# evm_1.net
KiCad netlist of a schematic drawn in EAGLE
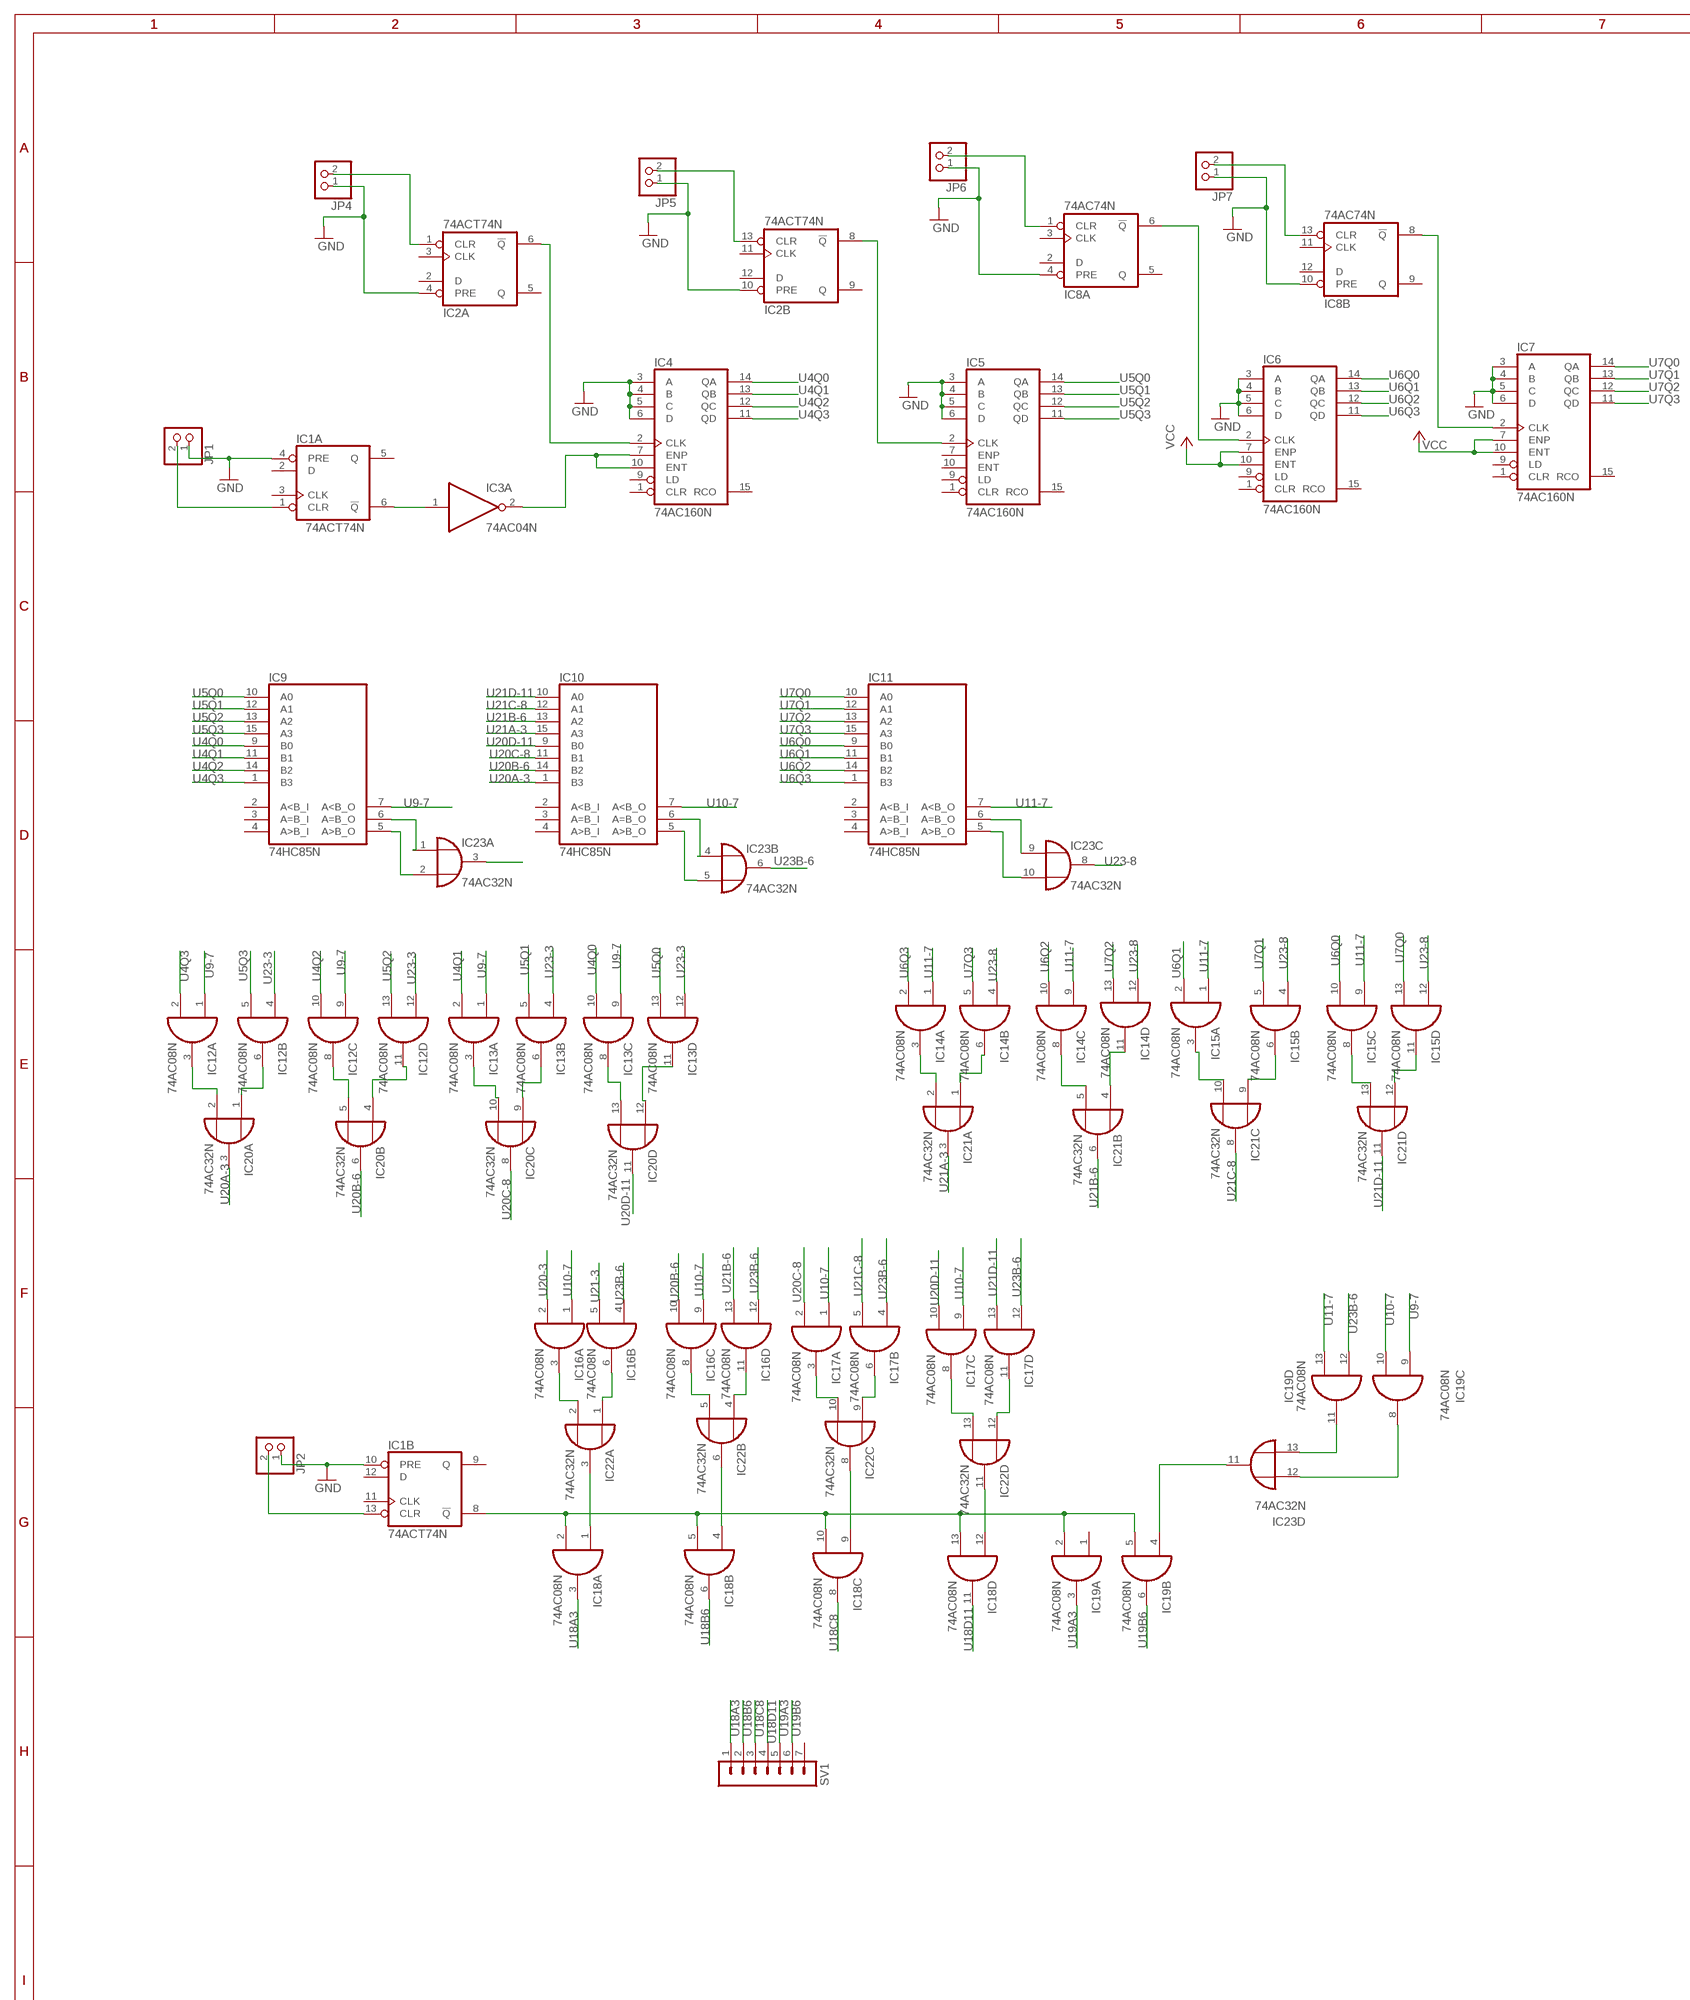
[diagram p0: schematic, sheet 1, part 1 of 2]
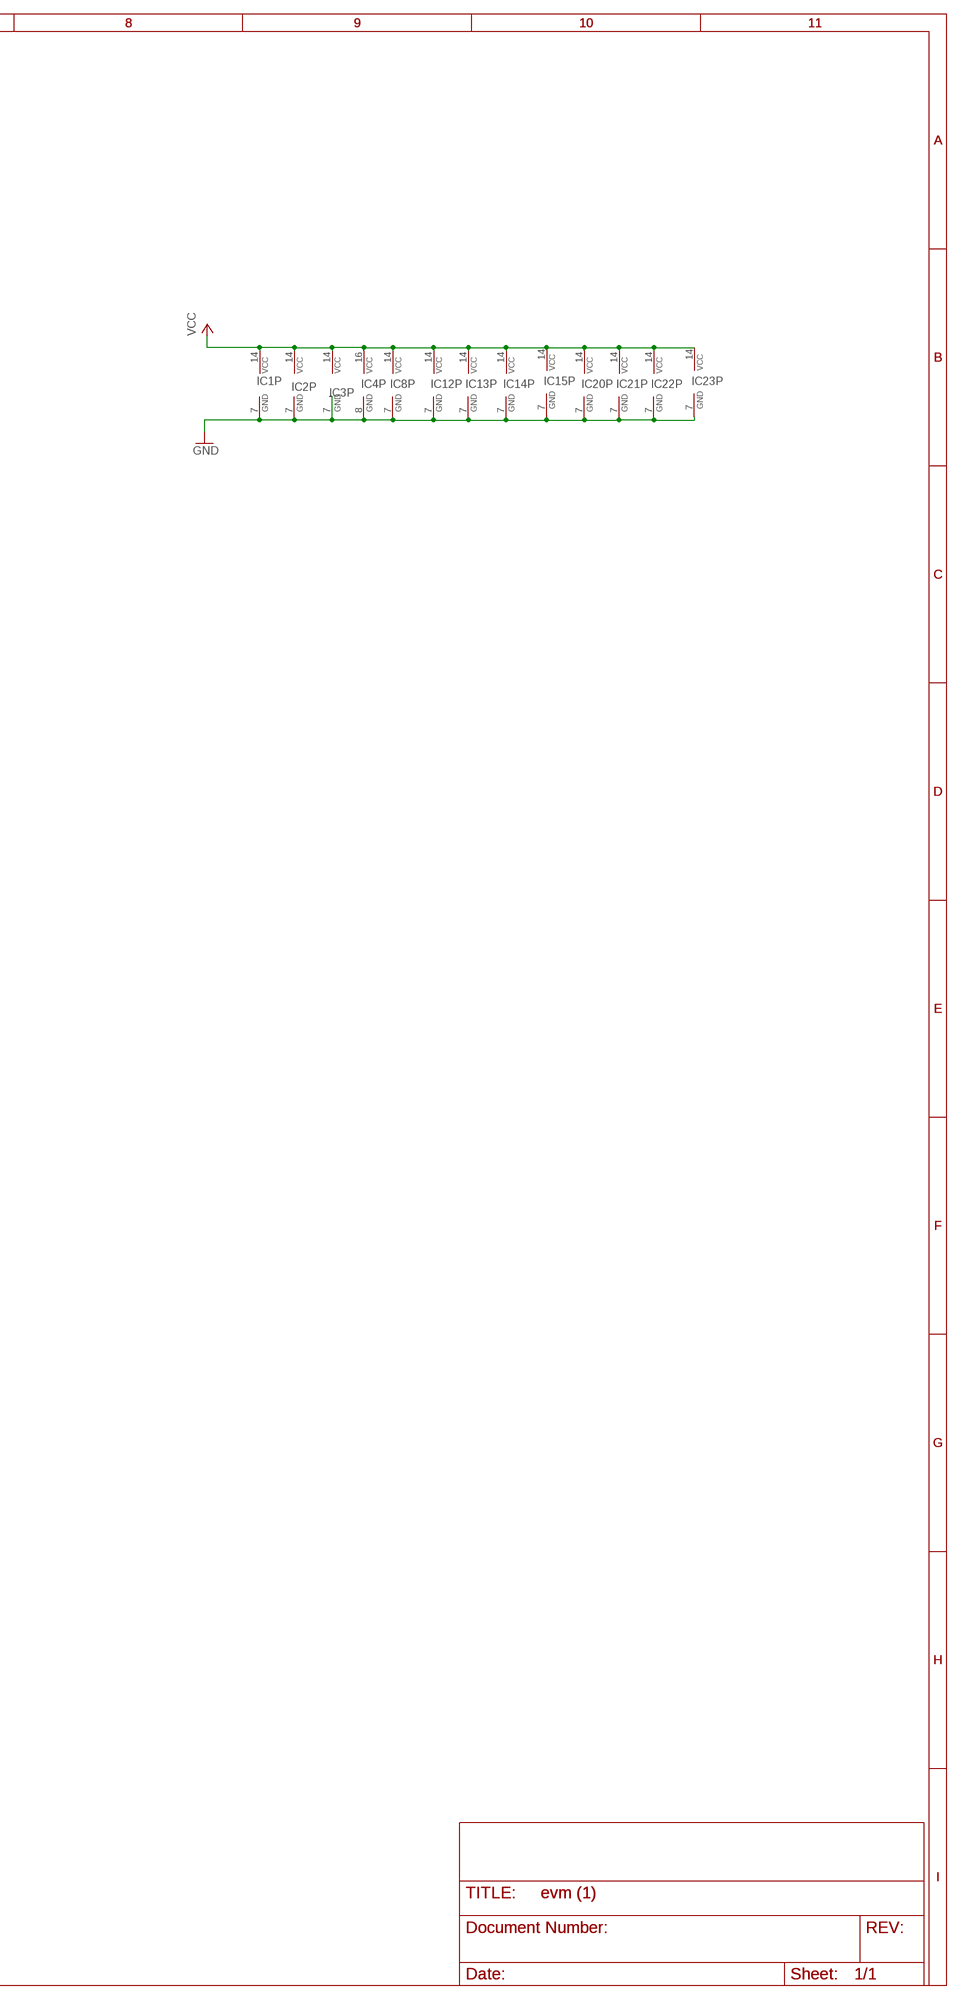
[diagram p1: schematic, sheet 1, part 2 of 2]

(export (version "E")
  (design (tool "Eeschema 10.0.6"))
  (components
    (comp (ref "IC1")
      (value "74ACT74N")
      (footprint "eagle-import:DIL14")
      (libsource (lib "eagle-import") (part "7474NACT"))
    )
    (comp (ref "IC2")
      (value "74ACT74N")
      (footprint "eagle-import:DIL14")
      (libsource (lib "eagle-import") (part "7474NACT"))
    )
    (comp (ref "IC3")
      (value "74AC04N")
      (footprint "eagle-import:DIL14")
      (libsource (lib "eagle-import") (part "7404NAC"))
    )
    (comp (ref "IC4")
      (value "74AC160N")
      (footprint "eagle-import:DIL16")
      (libsource (lib "eagle-import") (part "74160NAC"))
    )
    (comp (ref "IC5")
      (value "74AC160N")
      (footprint "eagle-import:DIL16")
      (libsource (lib "eagle-import") (part "74160NAC"))
    )
    (comp (ref "IC6")
      (value "74AC160N")
      (footprint "eagle-import:DIL16")
      (libsource (lib "eagle-import") (part "74160NAC"))
    )
    (comp (ref "IC7")
      (value "74AC160N")
      (footprint "eagle-import:DIL16")
      (libsource (lib "eagle-import") (part "74160NAC"))
    )
    (comp (ref "IC8")
      (value "74AC74N")
      (footprint "eagle-import:DIL14")
      (libsource (lib "eagle-import") (part "7474NAC"))
    )
    (comp (ref "IC9")
      (value "74HC85N")
      (footprint "eagle-import:DIL16")
      (libsource (lib "eagle-import") (part "7485NHC"))
    )
    (comp (ref "IC10")
      (value "74HC85N")
      (footprint "eagle-import:DIL16")
      (libsource (lib "eagle-import") (part "7485NHC"))
    )
    (comp (ref "IC11")
      (value "74HC85N")
      (footprint "eagle-import:DIL16")
      (libsource (lib "eagle-import") (part "7485NHC"))
    )
    (comp (ref "IC12")
      (value "74AC08N")
      (footprint "eagle-import:DIL14")
      (libsource (lib "eagle-import") (part "7408NAC"))
    )
    (comp (ref "IC13")
      (value "74AC08N")
      (footprint "eagle-import:DIL14")
      (libsource (lib "eagle-import") (part "7408NAC"))
    )
    (comp (ref "IC14")
      (value "74AC08N")
      (footprint "eagle-import:DIL14")
      (libsource (lib "eagle-import") (part "7408NAC"))
    )
    (comp (ref "IC15")
      (value "74AC08N")
      (footprint "eagle-import:DIL14")
      (libsource (lib "eagle-import") (part "7408NAC"))
    )
    (comp (ref "IC16")
      (value "74AC08N")
      (footprint "eagle-import:DIL14")
      (libsource (lib "eagle-import") (part "7408NAC"))
    )
    (comp (ref "IC17")
      (value "74AC08N")
      (footprint "eagle-import:DIL14")
      (libsource (lib "eagle-import") (part "7408NAC"))
    )
    (comp (ref "IC18")
      (value "74AC08N")
      (footprint "eagle-import:DIL14")
      (libsource (lib "eagle-import") (part "7408NAC"))
    )
    (comp (ref "IC19")
      (value "74AC08N")
      (footprint "eagle-import:DIL14")
      (libsource (lib "eagle-import") (part "7408NAC"))
    )
    (comp (ref "IC20")
      (value "74AC32N")
      (footprint "eagle-import:DIL14")
      (libsource (lib "eagle-import") (part "7432NAC"))
    )
    (comp (ref "IC21")
      (value "74AC32N")
      (footprint "eagle-import:DIL14")
      (libsource (lib "eagle-import") (part "7432NAC"))
    )
    (comp (ref "IC22")
      (value "74AC32N")
      (footprint "eagle-import:DIL14")
      (libsource (lib "eagle-import") (part "7432NAC"))
    )
    (comp (ref "IC23")
      (value "74AC32N")
      (footprint "eagle-import:DIL14")
      (libsource (lib "eagle-import") (part "7432NAC"))
    )
    (comp (ref "JP1")
      (value "PINHD-1X2")
      (footprint "eagle-import:1X02")
      (libsource (lib "eagle-import") (part "PINHD-1X2"))
    )
    (comp (ref "JP2")
      (value "PINHD-1X2")
      (footprint "eagle-import:1X02")
      (libsource (lib "eagle-import") (part "PINHD-1X2"))
    )
    (comp (ref "JP4")
      (value "PINHD-1X2")
      (footprint "eagle-import:1X02")
      (libsource (lib "eagle-import") (part "PINHD-1X2"))
    )
    (comp (ref "JP5")
      (value "PINHD-1X2")
      (footprint "eagle-import:1X02")
      (libsource (lib "eagle-import") (part "PINHD-1X2"))
    )
    (comp (ref "JP6")
      (value "PINHD-1X2")
      (footprint "eagle-import:1X02")
      (libsource (lib "eagle-import") (part "PINHD-1X2"))
    )
    (comp (ref "JP7")
      (value "PINHD-1X2")
      (footprint "eagle-import:1X02")
      (libsource (lib "eagle-import") (part "PINHD-1X2"))
    )
    (comp (ref "SV1")
      (value "MA07-1")
      (footprint "eagle-import:MA07-1")
      (libsource (lib "eagle-import") (part "MA07-1"))
    )
  )
  (nets
    (net (code "1") (name "/U4Q0") (class "Default")
      (node (ref "IC13") (pin "10") (pinfunction "I1_10") (pintype "input"))
      (node (ref "IC4") (pin "14") (pinfunction "QA_14") (pintype "output"))
      (node (ref "IC9") (pin "9") (pinfunction "B0_9") (pintype "input"))
    )
    (net (code "2") (name "/U4Q1") (class "Default")
      (node (ref "IC13") (pin "2") (pinfunction "I1_2") (pintype "input"))
      (node (ref "IC4") (pin "13") (pinfunction "QB_13") (pintype "output"))
      (node (ref "IC9") (pin "11") (pinfunction "B1_11") (pintype "input"))
    )
    (net (code "3") (name "/U4Q2") (class "Default")
      (node (ref "IC12") (pin "10") (pinfunction "I1_10") (pintype "input"))
      (node (ref "IC4") (pin "12") (pinfunction "QC_12") (pintype "output"))
      (node (ref "IC9") (pin "14") (pinfunction "B2_14") (pintype "input"))
    )
    (net (code "4") (name "/U4Q3") (class "Default")
      (node (ref "IC12") (pin "2") (pinfunction "I1_2") (pintype "input"))
      (node (ref "IC4") (pin "11") (pinfunction "QD_11") (pintype "output"))
      (node (ref "IC9") (pin "1") (pinfunction "B3_1") (pintype "input"))
    )
    (net (code "5") (name "/U5Q0") (class "Default")
      (node (ref "IC13") (pin "13") (pinfunction "I1_13") (pintype "input"))
      (node (ref "IC5") (pin "14") (pinfunction "QA_14") (pintype "output"))
      (node (ref "IC9") (pin "10") (pinfunction "A0_10") (pintype "input"))
    )
    (net (code "6") (name "/U5Q1") (class "Default")
      (node (ref "IC13") (pin "5") (pinfunction "I1_5") (pintype "input"))
      (node (ref "IC5") (pin "13") (pinfunction "QB_13") (pintype "output"))
      (node (ref "IC9") (pin "12") (pinfunction "A1_12") (pintype "input"))
    )
    (net (code "7") (name "/U5Q2") (class "Default")
      (node (ref "IC12") (pin "13") (pinfunction "I1_13") (pintype "input"))
      (node (ref "IC5") (pin "12") (pinfunction "QC_12") (pintype "output"))
      (node (ref "IC9") (pin "13") (pinfunction "A2_13") (pintype "input"))
    )
    (net (code "8") (name "/U5Q3") (class "Default")
      (node (ref "IC12") (pin "5") (pinfunction "I1_5") (pintype "input"))
      (node (ref "IC5") (pin "11") (pinfunction "QD_11") (pintype "output"))
      (node (ref "IC9") (pin "15") (pinfunction "A3_15") (pintype "input"))
    )
    (net (code "9") (name "/U6Q0") (class "Default")
      (node (ref "IC11") (pin "9") (pinfunction "B0_9") (pintype "input"))
      (node (ref "IC15") (pin "10") (pinfunction "I1_10") (pintype "input"))
      (node (ref "IC6") (pin "14") (pinfunction "QA_14") (pintype "output"))
    )
    (net (code "10") (name "/U6Q1") (class "Default")
      (node (ref "IC11") (pin "11") (pinfunction "B1_11") (pintype "input"))
      (node (ref "IC15") (pin "2") (pinfunction "I1_2") (pintype "input"))
      (node (ref "IC6") (pin "13") (pinfunction "QB_13") (pintype "output"))
    )
    (net (code "11") (name "/U6Q2") (class "Default")
      (node (ref "IC11") (pin "14") (pinfunction "B2_14") (pintype "input"))
      (node (ref "IC14") (pin "10") (pinfunction "I1_10") (pintype "input"))
      (node (ref "IC6") (pin "12") (pinfunction "QC_12") (pintype "output"))
    )
    (net (code "12") (name "/U6Q3") (class "Default")
      (node (ref "IC11") (pin "1") (pinfunction "B3_1") (pintype "input"))
      (node (ref "IC14") (pin "2") (pinfunction "I1_2") (pintype "input"))
      (node (ref "IC6") (pin "11") (pinfunction "QD_11") (pintype "output"))
    )
    (net (code "13") (name "/U7Q0") (class "Default")
      (node (ref "IC11") (pin "10") (pinfunction "A0_10") (pintype "input"))
      (node (ref "IC15") (pin "13") (pinfunction "I1_13") (pintype "input"))
      (node (ref "IC7") (pin "14") (pinfunction "QA_14") (pintype "output"))
    )
    (net (code "14") (name "/U7Q1") (class "Default")
      (node (ref "IC11") (pin "12") (pinfunction "A1_12") (pintype "input"))
      (node (ref "IC15") (pin "5") (pinfunction "I1_5") (pintype "input"))
      (node (ref "IC7") (pin "13") (pinfunction "QB_13") (pintype "output"))
    )
    (net (code "15") (name "/U7Q2") (class "Default")
      (node (ref "IC11") (pin "13") (pinfunction "A2_13") (pintype "input"))
      (node (ref "IC14") (pin "13") (pinfunction "I1_13") (pintype "input"))
      (node (ref "IC7") (pin "12") (pinfunction "QC_12") (pintype "output"))
    )
    (net (code "16") (name "/U7Q3") (class "Default")
      (node (ref "IC11") (pin "15") (pinfunction "A3_15") (pintype "input"))
      (node (ref "IC14") (pin "5") (pinfunction "I1_5") (pintype "input"))
      (node (ref "IC7") (pin "11") (pinfunction "QD_11") (pintype "output"))
    )
    (net (code "17") (name "/U9-7") (class "Default")
      (node (ref "IC12") (pin "1") (pinfunction "I0_1") (pintype "input"))
      (node (ref "IC12") (pin "9") (pinfunction "I0_9") (pintype "input"))
      (node (ref "IC13") (pin "1") (pinfunction "I0_1") (pintype "input"))
      (node (ref "IC13") (pin "9") (pinfunction "I0_9") (pintype "input"))
      (node (ref "IC19") (pin "9") (pinfunction "I0_9") (pintype "input"))
      (node (ref "IC9") (pin "7") (pinfunction "A<B_O_7") (pintype "output"))
    )
    (net (code "18") (name "/U10-7") (class "Default")
      (node (ref "IC10") (pin "7") (pinfunction "A<B_O_7") (pintype "output"))
      (node (ref "IC16") (pin "1") (pinfunction "I0_1") (pintype "input"))
      (node (ref "IC16") (pin "9") (pinfunction "I0_9") (pintype "input"))
      (node (ref "IC17") (pin "1") (pinfunction "I0_1") (pintype "input"))
      (node (ref "IC17") (pin "9") (pinfunction "I0_9") (pintype "input"))
      (node (ref "IC19") (pin "10") (pinfunction "I1_10") (pintype "input"))
    )
    (net (code "19") (name "/U11-7") (class "Default")
      (node (ref "IC11") (pin "7") (pinfunction "A<B_O_7") (pintype "output"))
      (node (ref "IC14") (pin "1") (pinfunction "I0_1") (pintype "input"))
      (node (ref "IC14") (pin "9") (pinfunction "I0_9") (pintype "input"))
      (node (ref "IC15") (pin "1") (pinfunction "I0_1") (pintype "input"))
      (node (ref "IC15") (pin "9") (pinfunction "I0_9") (pintype "input"))
      (node (ref "IC19") (pin "13") (pinfunction "I1_13") (pintype "input"))
    )
    (net (code "20") (name "/U18A3") (class "Default")
      (node (ref "IC18") (pin "3") (pinfunction "O_3") (pintype "output"))
      (node (ref "SV1") (pin "1") (pinfunction "1_1") (pintype "passive"))
    )
    (net (code "21") (name "/U18B6") (class "Default")
      (node (ref "IC18") (pin "6") (pinfunction "O_6") (pintype "output"))
      (node (ref "SV1") (pin "2") (pinfunction "2_2") (pintype "passive"))
    )
    (net (code "22") (name "/U18C8") (class "Default")
      (node (ref "IC18") (pin "8") (pinfunction "O_8") (pintype "output"))
      (node (ref "SV1") (pin "3") (pinfunction "3_3") (pintype "passive"))
    )
    (net (code "23") (name "/U18D11") (class "Default")
      (node (ref "IC18") (pin "11") (pinfunction "O_11") (pintype "output"))
      (node (ref "SV1") (pin "4") (pinfunction "4_4") (pintype "passive"))
    )
    (net (code "24") (name "/U19A3") (class "Default")
      (node (ref "IC19") (pin "3") (pinfunction "O_3") (pintype "output"))
      (node (ref "SV1") (pin "5") (pinfunction "5_5") (pintype "passive"))
    )
    (net (code "25") (name "/U19B6") (class "Default")
      (node (ref "IC19") (pin "6") (pinfunction "O_6") (pintype "output"))
      (node (ref "SV1") (pin "6") (pinfunction "6_6") (pintype "passive"))
    )
    (net (code "26") (name "/U20-3") (class "Default")
      (node (ref "IC16") (pin "2") (pinfunction "I1_2") (pintype "input"))
    )
    (net (code "27") (name "/U20A-3") (class "Default")
      (node (ref "IC10") (pin "1") (pinfunction "B3_1") (pintype "input"))
      (node (ref "IC20") (pin "3") (pinfunction "O_3") (pintype "output"))
    )
    (net (code "28") (name "/U20B-6") (class "Default")
      (node (ref "IC10") (pin "14") (pinfunction "B2_14") (pintype "input"))
      (node (ref "IC16") (pin "10") (pinfunction "I1_10") (pintype "input"))
      (node (ref "IC20") (pin "6") (pinfunction "O_6") (pintype "output"))
    )
    (net (code "29") (name "/U20C-8") (class "Default")
      (node (ref "IC10") (pin "11") (pinfunction "B1_11") (pintype "input"))
      (node (ref "IC17") (pin "2") (pinfunction "I1_2") (pintype "input"))
      (node (ref "IC20") (pin "8") (pinfunction "O_8") (pintype "output"))
    )
    (net (code "30") (name "/U20D-11") (class "Default")
      (node (ref "IC10") (pin "9") (pinfunction "B0_9") (pintype "input"))
      (node (ref "IC17") (pin "10") (pinfunction "I1_10") (pintype "input"))
      (node (ref "IC20") (pin "11") (pinfunction "O_11") (pintype "output"))
    )
    (net (code "31") (name "/U21-3") (class "Default")
      (node (ref "IC16") (pin "5") (pinfunction "I1_5") (pintype "input"))
    )
    (net (code "32") (name "/U21A-3") (class "Default")
      (node (ref "IC10") (pin "15") (pinfunction "A3_15") (pintype "input"))
      (node (ref "IC21") (pin "3") (pinfunction "O_3") (pintype "output"))
    )
    (net (code "33") (name "/U21B-6") (class "Default")
      (node (ref "IC10") (pin "13") (pinfunction "A2_13") (pintype "input"))
      (node (ref "IC16") (pin "13") (pinfunction "I1_13") (pintype "input"))
      (node (ref "IC21") (pin "6") (pinfunction "O_6") (pintype "output"))
    )
    (net (code "34") (name "/U21C-8") (class "Default")
      (node (ref "IC10") (pin "12") (pinfunction "A1_12") (pintype "input"))
      (node (ref "IC17") (pin "5") (pinfunction "I1_5") (pintype "input"))
      (node (ref "IC21") (pin "8") (pinfunction "O_8") (pintype "output"))
    )
    (net (code "35") (name "/U21D-11") (class "Default")
      (node (ref "IC10") (pin "10") (pinfunction "A0_10") (pintype "input"))
      (node (ref "IC17") (pin "13") (pinfunction "I1_13") (pintype "input"))
      (node (ref "IC21") (pin "11") (pinfunction "O_11") (pintype "output"))
    )
    (net (code "36") (name "/U23-3") (class "Default")
      (node (ref "IC12") (pin "12") (pinfunction "I0_12") (pintype "input"))
      (node (ref "IC12") (pin "4") (pinfunction "I0_4") (pintype "input"))
      (node (ref "IC13") (pin "12") (pinfunction "I0_12") (pintype "input"))
      (node (ref "IC13") (pin "4") (pinfunction "I0_4") (pintype "input"))
    )
    (net (code "37") (name "/U23-8") (class "Default")
      (node (ref "IC14") (pin "12") (pinfunction "I0_12") (pintype "input"))
      (node (ref "IC14") (pin "4") (pinfunction "I0_4") (pintype "input"))
      (node (ref "IC15") (pin "12") (pinfunction "I0_12") (pintype "input"))
      (node (ref "IC15") (pin "4") (pinfunction "I0_4") (pintype "input"))
      (node (ref "IC23") (pin "8") (pinfunction "O_8") (pintype "output"))
    )
    (net (code "38") (name "/U23B-6") (class "Default")
      (node (ref "IC16") (pin "12") (pinfunction "I0_12") (pintype "input"))
      (node (ref "IC16") (pin "4") (pinfunction "I0_4") (pintype "input"))
      (node (ref "IC17") (pin "12") (pinfunction "I0_12") (pintype "input"))
      (node (ref "IC17") (pin "4") (pinfunction "I0_4") (pintype "input"))
      (node (ref "IC19") (pin "12") (pinfunction "I0_12") (pintype "input"))
      (node (ref "IC23") (pin "6") (pinfunction "O_6") (pintype "output"))
    )
    (net (code "39") (name "GND") (class "Default")
      (node (ref "IC1") (pin "10") (pinfunction "PRE_10") (pintype "input"))
      (node (ref "IC1") (pin "4") (pinfunction "PRE_4") (pintype "input"))
      (node (ref "IC1") (pin "7") (pinfunction "GND_7") (pintype "power_in"))
      (node (ref "IC12") (pin "7") (pinfunction "GND_7") (pintype "power_in"))
      (node (ref "IC13") (pin "7") (pinfunction "GND_7") (pintype "power_in"))
      (node (ref "IC14") (pin "7") (pinfunction "GND_7") (pintype "power_in"))
      (node (ref "IC15") (pin "7") (pinfunction "GND_7") (pintype "power_in"))
      (node (ref "IC2") (pin "10") (pinfunction "PRE_10") (pintype "input"))
      (node (ref "IC2") (pin "4") (pinfunction "PRE_4") (pintype "input"))
      (node (ref "IC2") (pin "7") (pinfunction "GND_7") (pintype "power_in"))
      (node (ref "IC20") (pin "7") (pinfunction "GND_7") (pintype "power_in"))
      (node (ref "IC21") (pin "7") (pinfunction "GND_7") (pintype "power_in"))
      (node (ref "IC22") (pin "7") (pinfunction "GND_7") (pintype "power_in"))
      (node (ref "IC23") (pin "7") (pinfunction "GND_7") (pintype "power_in"))
      (node (ref "IC3") (pin "7") (pinfunction "GND_7") (pintype "power_in"))
      (node (ref "IC4") (pin "3") (pinfunction "A_3") (pintype "input"))
      (node (ref "IC4") (pin "4") (pinfunction "B_4") (pintype "input"))
      (node (ref "IC4") (pin "5") (pinfunction "C_5") (pintype "input"))
      (node (ref "IC4") (pin "6") (pinfunction "D_6") (pintype "input"))
      (node (ref "IC4") (pin "8") (pinfunction "GND_8") (pintype "power_in"))
      (node (ref "IC5") (pin "3") (pinfunction "A_3") (pintype "input"))
      (node (ref "IC5") (pin "4") (pinfunction "B_4") (pintype "input"))
      (node (ref "IC5") (pin "5") (pinfunction "C_5") (pintype "input"))
      (node (ref "IC5") (pin "6") (pinfunction "D_6") (pintype "input"))
      (node (ref "IC6") (pin "3") (pinfunction "A_3") (pintype "input"))
      (node (ref "IC6") (pin "4") (pinfunction "B_4") (pintype "input"))
      (node (ref "IC6") (pin "5") (pinfunction "C_5") (pintype "input"))
      (node (ref "IC6") (pin "6") (pinfunction "D_6") (pintype "input"))
      (node (ref "IC7") (pin "3") (pinfunction "A_3") (pintype "input"))
      (node (ref "IC7") (pin "4") (pinfunction "B_4") (pintype "input"))
      (node (ref "IC7") (pin "5") (pinfunction "C_5") (pintype "input"))
      (node (ref "IC7") (pin "6") (pinfunction "D_6") (pintype "input"))
      (node (ref "IC8") (pin "10") (pinfunction "PRE_10") (pintype "input"))
      (node (ref "IC8") (pin "4") (pinfunction "PRE_4") (pintype "input"))
      (node (ref "IC8") (pin "7") (pinfunction "GND_7") (pintype "power_in"))
      (node (ref "JP1") (pin "1") (pinfunction "1_1") (pintype "passive"))
      (node (ref "JP2") (pin "1") (pinfunction "1_1") (pintype "passive"))
      (node (ref "JP4") (pin "1") (pinfunction "1_1") (pintype "passive"))
      (node (ref "JP5") (pin "1") (pinfunction "1_1") (pintype "passive"))
      (node (ref "JP6") (pin "1") (pinfunction "1_1") (pintype "passive"))
      (node (ref "JP7") (pin "1") (pinfunction "1_1") (pintype "passive"))
    )
    (net (code "40") (name "Net-(IC1A-CLR)") (class "Default")
      (node (ref "IC1") (pin "1") (pinfunction "CLR_1") (pintype "input"))
      (node (ref "JP1") (pin "2") (pinfunction "2_2") (pintype "passive"))
    )
    (net (code "41") (name "Net-(IC1A-~{Q})") (class "Default")
      (node (ref "IC1") (pin "6") (pinfunction "~{Q}_6") (pintype "output"))
      (node (ref "IC3") (pin "1") (pinfunction "I_1") (pintype "input"))
    )
    (net (code "42") (name "Net-(IC1B-CLR)") (class "Default")
      (node (ref "IC1") (pin "13") (pinfunction "CLR_13") (pintype "input"))
      (node (ref "JP2") (pin "2") (pinfunction "2_2") (pintype "passive"))
    )
    (net (code "43") (name "Net-(IC2A-CLR)") (class "Default")
      (node (ref "IC2") (pin "1") (pinfunction "CLR_1") (pintype "input"))
      (node (ref "JP4") (pin "2") (pinfunction "2_2") (pintype "passive"))
    )
    (net (code "44") (name "Net-(IC2A-~{Q})") (class "Default")
      (node (ref "IC2") (pin "6") (pinfunction "~{Q}_6") (pintype "output"))
      (node (ref "IC4") (pin "2") (pinfunction "CLK_2") (pintype "input"))
    )
    (net (code "45") (name "Net-(IC2B-CLR)") (class "Default")
      (node (ref "IC2") (pin "13") (pinfunction "CLR_13") (pintype "input"))
      (node (ref "JP5") (pin "2") (pinfunction "2_2") (pintype "passive"))
    )
    (net (code "46") (name "Net-(IC2B-~{Q})") (class "Default")
      (node (ref "IC2") (pin "8") (pinfunction "~{Q}_8") (pintype "output"))
      (node (ref "IC5") (pin "2") (pinfunction "CLK_2") (pintype "input"))
    )
    (net (code "47") (name "Net-(IC3A-O)") (class "Default")
      (node (ref "IC3") (pin "2") (pinfunction "O_2") (pintype "output"))
      (node (ref "IC4") (pin "10") (pinfunction "ENT_10") (pintype "input"))
      (node (ref "IC4") (pin "7") (pinfunction "ENP_7") (pintype "input"))
    )
    (net (code "48") (name "Net-(IC6A-CLK)") (class "Default")
      (node (ref "IC6") (pin "2") (pinfunction "CLK_2") (pintype "input"))
      (node (ref "IC8") (pin "6") (pinfunction "~{Q}_6") (pintype "output"))
    )
    (net (code "49") (name "Net-(IC7A-CLK)") (class "Default")
      (node (ref "IC7") (pin "2") (pinfunction "CLK_2") (pintype "input"))
      (node (ref "IC8") (pin "8") (pinfunction "~{Q}_8") (pintype "output"))
    )
    (net (code "50") (name "Net-(IC7A-ENP)") (class "Default")
      (node (ref "IC7") (pin "10") (pinfunction "ENT_10") (pintype "input"))
      (node (ref "IC7") (pin "7") (pinfunction "ENP_7") (pintype "input"))
    )
    (net (code "51") (name "Net-(IC8A-CLR)") (class "Default")
      (node (ref "IC8") (pin "1") (pinfunction "CLR_1") (pintype "input"))
      (node (ref "JP6") (pin "2") (pinfunction "2_2") (pintype "passive"))
    )
    (net (code "52") (name "Net-(IC8B-CLR)") (class "Default")
      (node (ref "IC8") (pin "13") (pinfunction "CLR_13") (pintype "input"))
      (node (ref "JP7") (pin "2") (pinfunction "2_2") (pintype "passive"))
    )
    (net (code "53") (name "Net-(IC10A-A=B_O)") (class "Default")
      (node (ref "IC10") (pin "6") (pinfunction "A=B_O_6") (pintype "output"))
      (node (ref "IC23") (pin "4") (pinfunction "I0_4") (pintype "input"))
    )
    (net (code "54") (name "Net-(IC10A-A>B_O)") (class "Default")
      (node (ref "IC10") (pin "5") (pinfunction "A>B_O_5") (pintype "output"))
      (node (ref "IC23") (pin "5") (pinfunction "I1_5") (pintype "input"))
    )
    (net (code "55") (name "Net-(IC11A-A=B_O)") (class "Default")
      (node (ref "IC11") (pin "6") (pinfunction "A=B_O_6") (pintype "output"))
      (node (ref "IC23") (pin "9") (pinfunction "I0_9") (pintype "input"))
    )
    (net (code "56") (name "Net-(IC11A-A>B_O)") (class "Default")
      (node (ref "IC11") (pin "5") (pinfunction "A>B_O_5") (pintype "output"))
      (node (ref "IC23") (pin "10") (pinfunction "I1_10") (pintype "input"))
    )
    (net (code "57") (name "Net-(IC12A-O)") (class "Default")
      (node (ref "IC12") (pin "3") (pinfunction "O_3") (pintype "output"))
      (node (ref "IC20") (pin "2") (pinfunction "I1_2") (pintype "input"))
    )
    (net (code "58") (name "Net-(IC12B-O)") (class "Default")
      (node (ref "IC12") (pin "6") (pinfunction "O_6") (pintype "output"))
      (node (ref "IC20") (pin "1") (pinfunction "I0_1") (pintype "input"))
    )
    (net (code "59") (name "Net-(IC12C-O)") (class "Default")
      (node (ref "IC12") (pin "8") (pinfunction "O_8") (pintype "output"))
      (node (ref "IC20") (pin "5") (pinfunction "I1_5") (pintype "input"))
    )
    (net (code "60") (name "Net-(IC12D-O)") (class "Default")
      (node (ref "IC12") (pin "11") (pinfunction "O_11") (pintype "output"))
      (node (ref "IC20") (pin "4") (pinfunction "I0_4") (pintype "input"))
    )
    (net (code "61") (name "Net-(IC13A-O)") (class "Default")
      (node (ref "IC13") (pin "3") (pinfunction "O_3") (pintype "output"))
      (node (ref "IC20") (pin "10") (pinfunction "I1_10") (pintype "input"))
    )
    (net (code "62") (name "Net-(IC13B-O)") (class "Default")
      (node (ref "IC13") (pin "6") (pinfunction "O_6") (pintype "output"))
      (node (ref "IC20") (pin "9") (pinfunction "I0_9") (pintype "input"))
    )
    (net (code "63") (name "Net-(IC13C-O)") (class "Default")
      (node (ref "IC13") (pin "8") (pinfunction "O_8") (pintype "output"))
      (node (ref "IC20") (pin "13") (pinfunction "I1_13") (pintype "input"))
    )
    (net (code "64") (name "Net-(IC13D-O)") (class "Default")
      (node (ref "IC13") (pin "11") (pinfunction "O_11") (pintype "output"))
      (node (ref "IC20") (pin "12") (pinfunction "I0_12") (pintype "input"))
    )
    (net (code "65") (name "Net-(IC14A-O)") (class "Default")
      (node (ref "IC14") (pin "3") (pinfunction "O_3") (pintype "output"))
      (node (ref "IC21") (pin "2") (pinfunction "I1_2") (pintype "input"))
    )
    (net (code "66") (name "Net-(IC14B-O)") (class "Default")
      (node (ref "IC14") (pin "6") (pinfunction "O_6") (pintype "output"))
      (node (ref "IC21") (pin "1") (pinfunction "I0_1") (pintype "input"))
    )
    (net (code "67") (name "Net-(IC14C-O)") (class "Default")
      (node (ref "IC14") (pin "8") (pinfunction "O_8") (pintype "output"))
      (node (ref "IC21") (pin "5") (pinfunction "I1_5") (pintype "input"))
    )
    (net (code "68") (name "Net-(IC14D-O)") (class "Default")
      (node (ref "IC14") (pin "11") (pinfunction "O_11") (pintype "output"))
      (node (ref "IC21") (pin "4") (pinfunction "I0_4") (pintype "input"))
    )
    (net (code "69") (name "Net-(IC15A-O)") (class "Default")
      (node (ref "IC15") (pin "3") (pinfunction "O_3") (pintype "output"))
      (node (ref "IC21") (pin "10") (pinfunction "I1_10") (pintype "input"))
    )
    (net (code "70") (name "Net-(IC15B-O)") (class "Default")
      (node (ref "IC15") (pin "6") (pinfunction "O_6") (pintype "output"))
      (node (ref "IC21") (pin "9") (pinfunction "I0_9") (pintype "input"))
    )
    (net (code "71") (name "Net-(IC15C-O)") (class "Default")
      (node (ref "IC15") (pin "8") (pinfunction "O_8") (pintype "output"))
      (node (ref "IC21") (pin "13") (pinfunction "I1_13") (pintype "input"))
    )
    (net (code "72") (name "Net-(IC15D-O)") (class "Default")
      (node (ref "IC15") (pin "11") (pinfunction "O_11") (pintype "output"))
      (node (ref "IC21") (pin "12") (pinfunction "I0_12") (pintype "input"))
    )
    (net (code "73") (name "Net-(IC16A-O)") (class "Default")
      (node (ref "IC16") (pin "3") (pinfunction "O_3") (pintype "output"))
      (node (ref "IC22") (pin "2") (pinfunction "I1_2") (pintype "input"))
    )
    (net (code "74") (name "Net-(IC16B-O)") (class "Default")
      (node (ref "IC16") (pin "6") (pinfunction "O_6") (pintype "output"))
      (node (ref "IC22") (pin "1") (pinfunction "I0_1") (pintype "input"))
    )
    (net (code "75") (name "Net-(IC16C-O)") (class "Default")
      (node (ref "IC16") (pin "8") (pinfunction "O_8") (pintype "output"))
      (node (ref "IC22") (pin "5") (pinfunction "I1_5") (pintype "input"))
    )
    (net (code "76") (name "Net-(IC16D-O)") (class "Default")
      (node (ref "IC16") (pin "11") (pinfunction "O_11") (pintype "output"))
      (node (ref "IC22") (pin "4") (pinfunction "I0_4") (pintype "input"))
    )
    (net (code "77") (name "Net-(IC17A-O)") (class "Default")
      (node (ref "IC17") (pin "3") (pinfunction "O_3") (pintype "output"))
      (node (ref "IC22") (pin "10") (pinfunction "I1_10") (pintype "input"))
    )
    (net (code "78") (name "Net-(IC17B-O)") (class "Default")
      (node (ref "IC17") (pin "6") (pinfunction "O_6") (pintype "output"))
      (node (ref "IC22") (pin "9") (pinfunction "I0_9") (pintype "input"))
    )
    (net (code "79") (name "Net-(IC17C-O)") (class "Default")
      (node (ref "IC17") (pin "8") (pinfunction "O_8") (pintype "output"))
      (node (ref "IC22") (pin "13") (pinfunction "I1_13") (pintype "input"))
    )
    (net (code "80") (name "Net-(IC17D-O)") (class "Default")
      (node (ref "IC17") (pin "11") (pinfunction "O_11") (pintype "output"))
      (node (ref "IC22") (pin "12") (pinfunction "I0_12") (pintype "input"))
    )
    (net (code "81") (name "Net-(IC18A-I0)") (class "Default")
      (node (ref "IC18") (pin "1") (pinfunction "I0_1") (pintype "input"))
      (node (ref "IC22") (pin "3") (pinfunction "O_3") (pintype "output"))
    )
    (net (code "82") (name "Net-(IC18A-I1)") (class "Default")
      (node (ref "IC1") (pin "8") (pinfunction "~{Q}_8") (pintype "output"))
      (node (ref "IC18") (pin "10") (pinfunction "I1_10") (pintype "input"))
      (node (ref "IC18") (pin "13") (pinfunction "I1_13") (pintype "input"))
      (node (ref "IC18") (pin "2") (pinfunction "I1_2") (pintype "input"))
      (node (ref "IC18") (pin "5") (pinfunction "I1_5") (pintype "input"))
      (node (ref "IC19") (pin "2") (pinfunction "I1_2") (pintype "input"))
      (node (ref "IC19") (pin "5") (pinfunction "I1_5") (pintype "input"))
    )
    (net (code "83") (name "Net-(IC18B-I0)") (class "Default")
      (node (ref "IC18") (pin "4") (pinfunction "I0_4") (pintype "input"))
      (node (ref "IC22") (pin "6") (pinfunction "O_6") (pintype "output"))
    )
    (net (code "84") (name "Net-(IC18C-I0)") (class "Default")
      (node (ref "IC18") (pin "9") (pinfunction "I0_9") (pintype "input"))
      (node (ref "IC22") (pin "8") (pinfunction "O_8") (pintype "output"))
    )
    (net (code "85") (name "Net-(IC18D-I0)") (class "Default")
      (node (ref "IC18") (pin "12") (pinfunction "I0_12") (pintype "input"))
      (node (ref "IC22") (pin "11") (pinfunction "O_11") (pintype "output"))
    )
    (net (code "86") (name "Net-(IC19B-I0)") (class "Default")
      (node (ref "IC19") (pin "4") (pinfunction "I0_4") (pintype "input"))
      (node (ref "IC23") (pin "11") (pinfunction "O_11") (pintype "output"))
    )
    (net (code "87") (name "Net-(IC19C-O)") (class "Default")
      (node (ref "IC19") (pin "8") (pinfunction "O_8") (pintype "output"))
      (node (ref "IC23") (pin "12") (pinfunction "I0_12") (pintype "input"))
    )
    (net (code "88") (name "Net-(IC19D-O)") (class "Default")
      (node (ref "IC19") (pin "11") (pinfunction "O_11") (pintype "output"))
      (node (ref "IC23") (pin "13") (pinfunction "I1_13") (pintype "input"))
    )
    (net (code "89") (name "Net-(IC23A-I0)") (class "Default")
      (node (ref "IC23") (pin "1") (pinfunction "I0_1") (pintype "input"))
      (node (ref "IC9") (pin "6") (pinfunction "A=B_O_6") (pintype "output"))
    )
    (net (code "90") (name "Net-(IC23A-I1)") (class "Default")
      (node (ref "IC23") (pin "2") (pinfunction "I1_2") (pintype "input"))
      (node (ref "IC9") (pin "5") (pinfunction "A>B_O_5") (pintype "output"))
    )
    (net (code "91") (name "VCC") (class "Default")
      (node (ref "IC1") (pin "14") (pinfunction "VCC_14") (pintype "power_in"))
      (node (ref "IC12") (pin "14") (pinfunction "VCC_14") (pintype "power_in"))
      (node (ref "IC13") (pin "14") (pinfunction "VCC_14") (pintype "power_in"))
      (node (ref "IC14") (pin "14") (pinfunction "VCC_14") (pintype "power_in"))
      (node (ref "IC15") (pin "14") (pinfunction "VCC_14") (pintype "power_in"))
      (node (ref "IC2") (pin "14") (pinfunction "VCC_14") (pintype "power_in"))
      (node (ref "IC20") (pin "14") (pinfunction "VCC_14") (pintype "power_in"))
      (node (ref "IC21") (pin "14") (pinfunction "VCC_14") (pintype "power_in"))
      (node (ref "IC22") (pin "14") (pinfunction "VCC_14") (pintype "power_in"))
      (node (ref "IC23") (pin "14") (pinfunction "VCC_14") (pintype "power_in"))
      (node (ref "IC3") (pin "14") (pinfunction "VCC_14") (pintype "power_in"))
      (node (ref "IC4") (pin "16") (pinfunction "VCC_16") (pintype "power_in"))
      (node (ref "IC6") (pin "10") (pinfunction "ENT_10") (pintype "input"))
      (node (ref "IC6") (pin "7") (pinfunction "ENP_7") (pintype "input"))
      (node (ref "IC8") (pin "14") (pinfunction "VCC_14") (pintype "power_in"))
    )
    (net (code "92") (name "unconnected-(IC1A-CLK-Pad3)") (class "Default")
      (node (ref "IC1") (pin "3") (pinfunction "CLK_3") (pintype "input"))
    )
    (net (code "93") (name "unconnected-(IC1A-D-Pad2)") (class "Default")
      (node (ref "IC1") (pin "2") (pinfunction "D_2") (pintype "input"))
    )
    (net (code "94") (name "unconnected-(IC1A-Q-Pad5)") (class "Default")
      (node (ref "IC1") (pin "5") (pinfunction "Q_5") (pintype "output"))
    )
    (net (code "95") (name "unconnected-(IC1B-CLK-Pad11)") (class "Default")
      (node (ref "IC1") (pin "11") (pinfunction "CLK_11") (pintype "input"))
    )
    (net (code "96") (name "unconnected-(IC1B-D-Pad12)") (class "Default")
      (node (ref "IC1") (pin "12") (pinfunction "D_12") (pintype "input"))
    )
    (net (code "97") (name "unconnected-(IC1B-Q-Pad9)") (class "Default")
      (node (ref "IC1") (pin "9") (pinfunction "Q_9") (pintype "output"))
    )
    (net (code "98") (name "unconnected-(IC2A-CLK-Pad3)") (class "Default")
      (node (ref "IC2") (pin "3") (pinfunction "CLK_3") (pintype "input"))
    )
    (net (code "99") (name "unconnected-(IC2A-D-Pad2)") (class "Default")
      (node (ref "IC2") (pin "2") (pinfunction "D_2") (pintype "input"))
    )
    (net (code "100") (name "unconnected-(IC2A-Q-Pad5)") (class "Default")
      (node (ref "IC2") (pin "5") (pinfunction "Q_5") (pintype "output"))
    )
    (net (code "101") (name "unconnected-(IC2B-CLK-Pad11)") (class "Default")
      (node (ref "IC2") (pin "11") (pinfunction "CLK_11") (pintype "input"))
    )
    (net (code "102") (name "unconnected-(IC2B-D-Pad12)") (class "Default")
      (node (ref "IC2") (pin "12") (pinfunction "D_12") (pintype "input"))
    )
    (net (code "103") (name "unconnected-(IC2B-Q-Pad9)") (class "Default")
      (node (ref "IC2") (pin "9") (pinfunction "Q_9") (pintype "output"))
    )
    (net (code "104") (name "unconnected-(IC4A-CLR-Pad1)") (class "Default")
      (node (ref "IC4") (pin "1") (pinfunction "CLR_1") (pintype "input"))
    )
    (net (code "105") (name "unconnected-(IC4A-LD-Pad9)") (class "Default")
      (node (ref "IC4") (pin "9") (pinfunction "LD_9") (pintype "input"))
    )
    (net (code "106") (name "unconnected-(IC4A-RCO-Pad15)") (class "Default")
      (node (ref "IC4") (pin "15") (pinfunction "RCO_15") (pintype "output"))
    )
    (net (code "107") (name "unconnected-(IC5A-CLR-Pad1)") (class "Default")
      (node (ref "IC5") (pin "1") (pinfunction "CLR_1") (pintype "input"))
    )
    (net (code "108") (name "unconnected-(IC5A-ENP-Pad7)") (class "Default")
      (node (ref "IC5") (pin "7") (pinfunction "ENP_7") (pintype "input"))
    )
    (net (code "109") (name "unconnected-(IC5A-ENT-Pad10)") (class "Default")
      (node (ref "IC5") (pin "10") (pinfunction "ENT_10") (pintype "input"))
    )
    (net (code "110") (name "unconnected-(IC5A-LD-Pad9)") (class "Default")
      (node (ref "IC5") (pin "9") (pinfunction "LD_9") (pintype "input"))
    )
    (net (code "111") (name "unconnected-(IC5A-RCO-Pad15)") (class "Default")
      (node (ref "IC5") (pin "15") (pinfunction "RCO_15") (pintype "output"))
    )
    (net (code "112") (name "unconnected-(IC6A-CLR-Pad1)") (class "Default")
      (node (ref "IC6") (pin "1") (pinfunction "CLR_1") (pintype "input"))
    )
    (net (code "113") (name "unconnected-(IC6A-LD-Pad9)") (class "Default")
      (node (ref "IC6") (pin "9") (pinfunction "LD_9") (pintype "input"))
    )
    (net (code "114") (name "unconnected-(IC6A-RCO-Pad15)") (class "Default")
      (node (ref "IC6") (pin "15") (pinfunction "RCO_15") (pintype "output"))
    )
    (net (code "115") (name "unconnected-(IC7A-CLR-Pad1)") (class "Default")
      (node (ref "IC7") (pin "1") (pinfunction "CLR_1") (pintype "input"))
    )
    (net (code "116") (name "unconnected-(IC7A-LD-Pad9)") (class "Default")
      (node (ref "IC7") (pin "9") (pinfunction "LD_9") (pintype "input"))
    )
    (net (code "117") (name "unconnected-(IC7A-RCO-Pad15)") (class "Default")
      (node (ref "IC7") (pin "15") (pinfunction "RCO_15") (pintype "output"))
    )
    (net (code "118") (name "unconnected-(IC8A-CLK-Pad3)") (class "Default")
      (node (ref "IC8") (pin "3") (pinfunction "CLK_3") (pintype "input"))
    )
    (net (code "119") (name "unconnected-(IC8A-D-Pad2)") (class "Default")
      (node (ref "IC8") (pin "2") (pinfunction "D_2") (pintype "input"))
    )
    (net (code "120") (name "unconnected-(IC8A-Q-Pad5)") (class "Default")
      (node (ref "IC8") (pin "5") (pinfunction "Q_5") (pintype "output"))
    )
    (net (code "121") (name "unconnected-(IC8B-CLK-Pad11)") (class "Default")
      (node (ref "IC8") (pin "11") (pinfunction "CLK_11") (pintype "input"))
    )
    (net (code "122") (name "unconnected-(IC8B-D-Pad12)") (class "Default")
      (node (ref "IC8") (pin "12") (pinfunction "D_12") (pintype "input"))
    )
    (net (code "123") (name "unconnected-(IC8B-Q-Pad9)") (class "Default")
      (node (ref "IC8") (pin "9") (pinfunction "Q_9") (pintype "output"))
    )
    (net (code "124") (name "unconnected-(IC9A-A<B_I-Pad2)") (class "Default")
      (node (ref "IC9") (pin "2") (pinfunction "A<B_I_2") (pintype "input"))
    )
    (net (code "125") (name "unconnected-(IC9A-A=B_I-Pad3)") (class "Default")
      (node (ref "IC9") (pin "3") (pinfunction "A=B_I_3") (pintype "input"))
    )
    (net (code "126") (name "unconnected-(IC9A-A>B_I-Pad4)") (class "Default")
      (node (ref "IC9") (pin "4") (pinfunction "A>B_I_4") (pintype "input"))
    )
    (net (code "127") (name "unconnected-(IC10A-A<B_I-Pad2)") (class "Default")
      (node (ref "IC10") (pin "2") (pinfunction "A<B_I_2") (pintype "input"))
    )
    (net (code "128") (name "unconnected-(IC10A-A=B_I-Pad3)") (class "Default")
      (node (ref "IC10") (pin "3") (pinfunction "A=B_I_3") (pintype "input"))
    )
    (net (code "129") (name "unconnected-(IC10A-A>B_I-Pad4)") (class "Default")
      (node (ref "IC10") (pin "4") (pinfunction "A>B_I_4") (pintype "input"))
    )
    (net (code "130") (name "unconnected-(IC11A-A<B_I-Pad2)") (class "Default")
      (node (ref "IC11") (pin "2") (pinfunction "A<B_I_2") (pintype "input"))
    )
    (net (code "131") (name "unconnected-(IC11A-A=B_I-Pad3)") (class "Default")
      (node (ref "IC11") (pin "3") (pinfunction "A=B_I_3") (pintype "input"))
    )
    (net (code "132") (name "unconnected-(IC11A-A>B_I-Pad4)") (class "Default")
      (node (ref "IC11") (pin "4") (pinfunction "A>B_I_4") (pintype "input"))
    )
    (net (code "133") (name "unconnected-(IC19A-I0-Pad1)") (class "Default")
      (node (ref "IC19") (pin "1") (pinfunction "I0_1") (pintype "input"))
    )
    (net (code "134") (name "unconnected-(IC23A-O-Pad3)") (class "Default")
      (node (ref "IC23") (pin "3") (pinfunction "O_3") (pintype "output"))
    )
    (net (code "135") (name "unconnected-(SV1-Pad7)") (class "Default")
      (node (ref "SV1") (pin "7") (pinfunction "7_7") (pintype "passive"))
    )
  )
)
